# source_of_current_hall_crossboard_1_1.net
KiCad netlist of a schematic drawn in Altium Designer
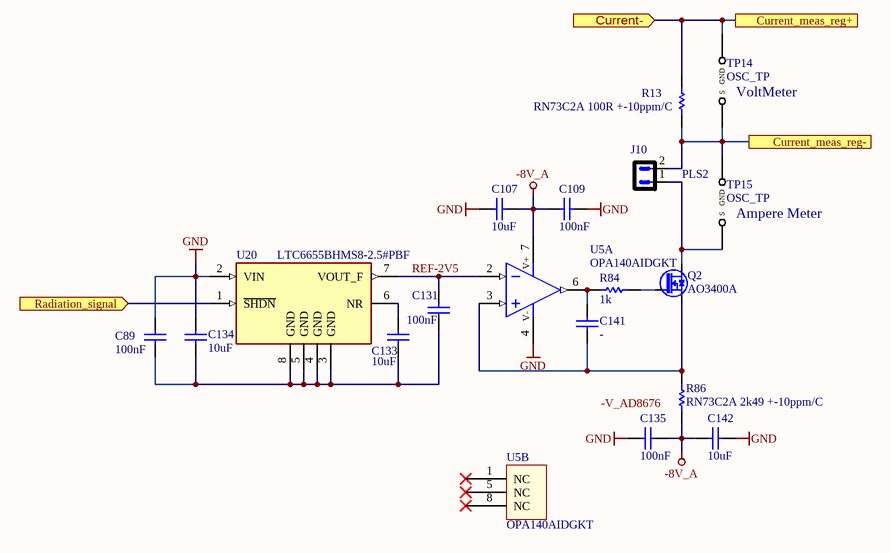
[diagram p0: source_of_current_hall_crossboard_1_1.SchDoc]

(export (version "E")
  (design (tool "Eeschema 10.0.6"))
  (components
    (comp (ref "C89")
      (value "100nF")
      (footprint "hall_crossboard_1_1_library:0603C")
      (description "Capacitor 0402 / 0603 / 0805")
      (libsource (lib "hall_crossboard_1_1_library") (part "Capacitor_ST"))
    )
    (comp (ref "C107")
      (value "10uF")
      (footprint "hall_crossboard_1_1_library:0805C")
      (description "Capacitor 0402 / 0603 / 0805")
      (libsource (lib "hall_crossboard_1_1_library") (part "Capacitor_ST"))
    )
    (comp (ref "C109")
      (value "100nF")
      (footprint "hall_crossboard_1_1_library:0603C")
      (description "Capacitor 0402 / 0603 / 0805")
      (libsource (lib "hall_crossboard_1_1_library") (part "Capacitor_ST"))
    )
    (comp (ref "C131")
      (value "100nF")
      (footprint "hall_crossboard_1_1_library:0603C")
      (description "Capacitor 0402 / 0603 / 0805")
      (libsource (lib "hall_crossboard_1_1_library") (part "Capacitor_ST"))
    )
    (comp (ref "C133")
      (value "10uF")
      (footprint "hall_crossboard_1_1_library:0805C")
      (description "Capacitor 0402 / 0603 / 0805")
      (libsource (lib "hall_crossboard_1_1_library") (part "Capacitor_ST"))
    )
    (comp (ref "C134")
      (value "10uF")
      (footprint "hall_crossboard_1_1_library:0805C")
      (description "Capacitor 0402 / 0603 / 0805")
      (libsource (lib "hall_crossboard_1_1_library") (part "Capacitor_ST"))
    )
    (comp (ref "C135")
      (value "100nF")
      (footprint "hall_crossboard_1_1_library:0603C")
      (description "Capacitor 0402 / 0603 / 0805")
      (libsource (lib "hall_crossboard_1_1_library") (part "Capacitor_ST"))
    )
    (comp (ref "C141")
      (value "-")
      (footprint "hall_crossboard_1_1_library:0603C")
      (description "Capacitor 0402 / 0603 / 0805")
      (libsource (lib "hall_crossboard_1_1") (part "Capacitor_ST"))
    )
    (comp (ref "C142")
      (value "10uF")
      (footprint "0805C")
      (description "Capacitor 0402 / 0603 / 0805")
      (libsource (lib "hall_crossboard_1_1_library") (part "Capacitor_ST"))
    )
    (comp (ref "J10")
      (value "PLS2")
      (footprint "footprint_hall_crossboard_1_1_library:SAMTEC_TSW-102-23-L-S")
      (libsource (lib "hall_crossboard_1_1") (part "PLS2"))
    )
    (comp (ref "Q2")
      (value "AO3400A")
      (footprint "SOT95P229X119-3N")
      (description "NMOS")
      (fields (field (name "VOLTAGE") "30V"))
      (libsource (lib "schematic_hall_crossboard_1_1_library") (part "AO3400A"))
    )
    (comp (ref "R13")
      (value "RN73C2A 100R +-10ppm/C")
      (footprint "0805R")
      (description "Resistor 0402 / 0603 / 0805")
      (libsource (lib "hall_crossboard_1_1_library") (part "Resistor_ST"))
    )
    (comp (ref "R84")
      (value "1k")
      (footprint "0805R")
      (description "Resistor 0402 / 0603 / 080")
      (libsource (lib "hall_crossboard_1_1_library") (part "Resistor_ST"))
    )
    (comp (ref "R86")
      (value "RN73C2A 2k49 +-10ppm/C")
      (footprint "0805R")
      (description "Resistor 0402 / 0603 / 0805")
      (libsource (lib "hall_crossboard_1_1_library") (part "Resistor_ST"))
    )
    (comp (ref "TP14")
      (value "OSC_TP")
      (footprint "hall_crossboard_1_1_library:TP2")
      (description "Контрольная точка для подключения осциллографа короткой землёй")
      (libsource (lib "hall_crossboard_1_1") (part "OscTP"))
    )
    (comp (ref "TP15")
      (value "OSC_TP")
      (footprint "hall_crossboard_1_1_library:TP2")
      (description "Контрольная точка для подключения осциллографа короткой землёй")
      (libsource (lib "hall_crossboard_1_1") (part "OscTP"))
    )
    (comp (ref "U5")
      (value "OPA140AIDGKT")
      (footprint "footprint_hall_crossboard_1_1_library:SOP65P490X110-8N")
      (fields (field (name "MF") "Texas Instruments"))
      (libsource (lib "schematic_hall_crossboard_1_1_library") (part "OPA140AIDGKT"))
    )
    (comp (ref "U20")
      (value "LTC6655BHMS8-2.5#PBF")
      (footprint "SOP65P490X110-8N")
      (description "Series Voltage Reference IC Fixed 5V V Â±0.025% 5 mA 8-MSOP")
      (fields (field (name "MF") "Analog Devices") (field (name "MP") "LTC6655BHMS8-5#PBF"))
      (libsource (lib "hall_crossboard_1_1_library") (part "LTC6655BHMS8-5#PBF"))
    )
  )
  (nets
    (net (code "1") (name "-8V_A") (class "Default")
      (node (ref "C107") (pin "1") (pinfunction "1_1") (pintype "passive"))
      (node (ref "C109") (pin "1") (pinfunction "1_1") (pintype "passive"))
      (node (ref "C135") (pin "1") (pinfunction "1_1") (pintype "passive"))
      (node (ref "C142") (pin "1") (pinfunction "1_1") (pintype "passive"))
      (node (ref "R86") (pin "1") (pinfunction "1_1") (pintype "passive"))
      (node (ref "U5") (pin "7") (pinfunction "V+_7") (pintype "power_in"))
    )
    (net (code "3") (name "/Current-") (class "Default")
      (node (ref "R13") (pin "2") (pinfunction "2_2") (pintype "passive"))
      (node (ref "TP14") (pin "2") (pinfunction "GND_2") (pintype "passive"))
    )
    (net (code "4") (name "/Current_meas_reg-") (class "Default")
      (node (ref "J10") (pin "2") (pinfunction "2_2") (pintype "bidirectional"))
      (node (ref "R13") (pin "1") (pinfunction "1_1") (pintype "passive"))
      (node (ref "TP14") (pin "1") (pinfunction "S_1") (pintype "passive"))
      (node (ref "TP15") (pin "2") (pinfunction "GND_2") (pintype "passive"))
    )
    (net (code "5") (name "/REF-2V5") (class "Default")
      (node (ref "C131") (pin "2") (pinfunction "2_2") (pintype "passive"))
      (node (ref "U20") (pin "7") (pinfunction "VOUT_F_7") (pintype "output"))
      (node (ref "U5") (pin "2") (pinfunction "IN-_2") (pintype "input"))
    )
    (net (code "6") (name "/Radiation_signal") (class "Default")
      (node (ref "U20") (pin "1") (pinfunction "~{SHDN}_1") (pintype "input"))
    )
    (net (code "7") (name "GND") (class "Default")
      (node (ref "C107") (pin "2") (pinfunction "2_2") (pintype "passive"))
      (node (ref "C109") (pin "2") (pinfunction "2_2") (pintype "passive"))
      (node (ref "C134") (pin "2") (pinfunction "2_2") (pintype "passive"))
      (node (ref "C135") (pin "2") (pinfunction "2_2") (pintype "passive"))
      (node (ref "C142") (pin "2") (pinfunction "2_2") (pintype "passive"))
      (node (ref "C89") (pin "2") (pinfunction "2_2") (pintype "passive"))
      (node (ref "U20") (pin "2") (pinfunction "VIN_2") (pintype "input"))
      (node (ref "U5") (pin "4") (pinfunction "V-_4") (pintype "power_in"))
    )
    (net (code "8") (name "Net-(C131-Pad1)") (class "Default")
      (node (ref "C131") (pin "1") (pinfunction "1_1") (pintype "passive"))
      (node (ref "C133") (pin "1") (pinfunction "1_1") (pintype "passive"))
      (node (ref "C134") (pin "1") (pinfunction "1_1") (pintype "passive"))
      (node (ref "C89") (pin "1") (pinfunction "1_1") (pintype "passive"))
      (node (ref "U20") (pin "3") (pinfunction "GND_3") (pintype "power_in"))
      (node (ref "U20") (pin "4") (pinfunction "GND_4") (pintype "power_in"))
      (node (ref "U20") (pin "5") (pinfunction "GND_5") (pintype "power_in"))
      (node (ref "U20") (pin "8") (pinfunction "GND_8") (pintype "power_in"))
    )
    (net (code "9") (name "Net-(Q2-D)") (class "Default")
      (node (ref "J10") (pin "1") (pinfunction "1_1") (pintype "bidirectional"))
      (node (ref "Q2") (pin "3") (pinfunction "D_3") (pintype "passive"))
      (node (ref "TP15") (pin "1") (pinfunction "S_1") (pintype "passive"))
    )
    (net (code "10") (name "Net-(Q2-G)") (class "Default")
      (node (ref "Q2") (pin "1") (pinfunction "G_1") (pintype "passive"))
      (node (ref "R84") (pin "2") (pinfunction "2_2") (pintype "passive"))
    )
    (net (code "11") (name "Net-(Q2-S)") (class "Default")
      (node (ref "C141") (pin "1") (pinfunction "1_1") (pintype "passive"))
      (node (ref "Q2") (pin "2") (pinfunction "S_2") (pintype "passive"))
      (node (ref "R86") (pin "2") (pinfunction "2_2") (pintype "passive"))
      (node (ref "U5") (pin "3") (pinfunction "IN+_3") (pintype "input"))
    )
    (net (code "12") (name "Net-(U5A-OUT)") (class "Default")
      (node (ref "C141") (pin "2") (pinfunction "2_2") (pintype "passive"))
      (node (ref "R84") (pin "1") (pinfunction "1_1") (pintype "passive"))
      (node (ref "U5") (pin "6") (pinfunction "OUT_6") (pintype "output"))
    )
    (net (code "13") (name "Net-(U20-NR)") (class "Default")
      (node (ref "C133") (pin "2") (pinfunction "2_2") (pintype "passive"))
      (node (ref "U20") (pin "6") (pinfunction "NR_6") (pintype "passive"))
    )
    (net (code "14") (name "unconnected-(U5B-NC-Pad1)") (class "Default")
      (node (ref "U5") (pin "1") (pinfunction "NC_1") (pintype "passive+no_connect"))
    )
    (net (code "15") (name "unconnected-(U5B-NC-Pad5)") (class "Default")
      (node (ref "U5") (pin "5") (pinfunction "NC_5") (pintype "passive+no_connect"))
    )
    (net (code "16") (name "unconnected-(U5B-NC-Pad8)") (class "Default")
      (node (ref "U5") (pin "8") (pinfunction "NC_8") (pintype "passive+no_connect"))
    )
  )
)
